# ATTiny85_Programmer_Arduino_Shield.net
KiCad netlist of a schematic drawn in EAGLE
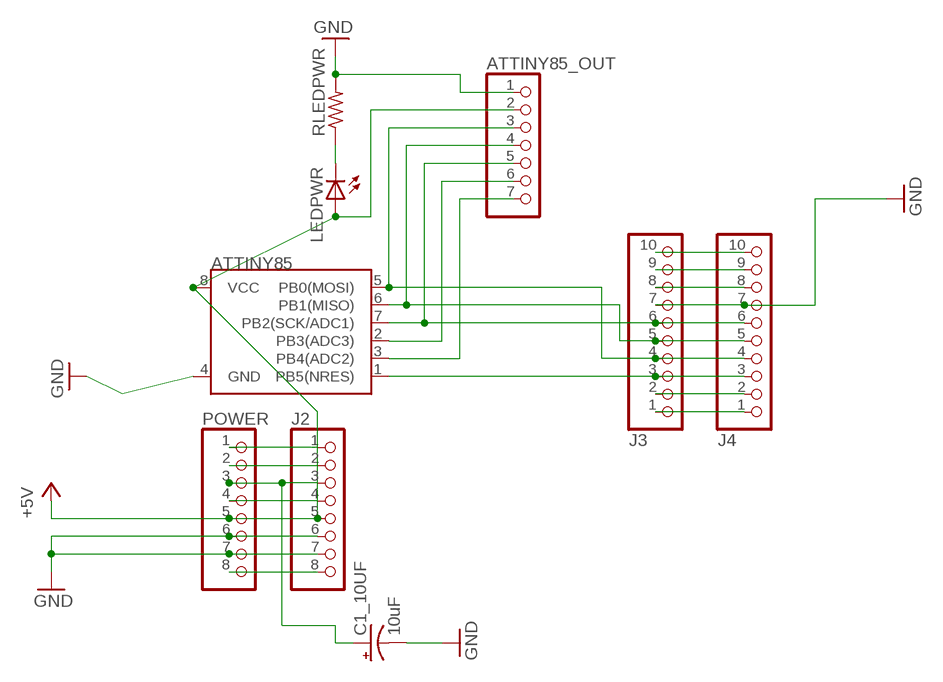
[diagram p0: schematic, sheet 1]

(export (version "E")
  (design (tool "Eeschema 10.0.6"))
  (components
    (comp (ref "ATTINY85")
      (value "TINY85-20-DIP")
      (footprint "eagle-import:DIP08")
      (libsource (lib "eagle-import") (part "ATTINY45TINY85-20-DIP"))
    )
    (comp (ref "ATTINY85_OUT")
      (value "PINHD-1X7")
      (footprint "eagle-import:1X07")
      (libsource (lib "eagle-import") (part "PINHD-1X7"))
    )
    (comp (ref "C1_10UF")
      (value "10uF")
      (footprint "eagle-import:EIA3216")
      (libsource (lib "eagle-import") (part "10UF-16V-10%(TANT)"))
    )
    (comp (ref "J2")
      (value "PINHD-1X8TH")
      (footprint "eagle-import:1X08-TH")
      (libsource (lib "eagle-import") (part "PINHD-1X8TH"))
    )
    (comp (ref "J3")
      (value "PINHD-1X10TH")
      (footprint "eagle-import:1X10-TH")
      (libsource (lib "eagle-import") (part "PINHD-1X10TH"))
    )
    (comp (ref "J4")
      (value "PINHD-1X10TH")
      (footprint "eagle-import:1X10-TH")
      (libsource (lib "eagle-import") (part "PINHD-1X10TH"))
    )
    (comp (ref "LEDPWR")
      (value "LEDCHIPLED_0805")
      (footprint "eagle-import:CHIPLED_0805")
      (libsource (lib "eagle-import") (part "LEDCHIPLED_0805"))
    )
    (comp (ref "POWER")
      (value "PINHD-1X8TH")
      (footprint "eagle-import:1X08-TH")
      (libsource (lib "eagle-import") (part "PINHD-1X8TH"))
    )
    (comp (ref "RLEDPWR")
      (value "R-US_R0805")
      (footprint "eagle-import:R0805")
      (libsource (lib "eagle-import") (part "R-US_R0805"))
    )
  )
  (nets
    (net (code "1") (name "+5V") (class "Default")
      (node (ref "ATTINY85") (pin "8") (pinfunction "VCC_8") (pintype "bidirectional"))
      (node (ref "ATTINY85_OUT") (pin "2") (pinfunction "2_2") (pintype "passive"))
      (node (ref "J2") (pin "5") (pinfunction "5_5") (pintype "passive"))
      (node (ref "LEDPWR") (pin "A") (pinfunction "A_A") (pintype "passive"))
      (node (ref "POWER") (pin "5") (pinfunction "5_5") (pintype "passive"))
    )
    (net (code "2") (name "GND") (class "Default")
      (node (ref "ATTINY85") (pin "4") (pinfunction "GND_4") (pintype "bidirectional"))
      (node (ref "ATTINY85_OUT") (pin "1") (pinfunction "1_1") (pintype "passive"))
      (node (ref "C1_10UF") (pin "C") (pinfunction "-_C") (pintype "passive"))
      (node (ref "J2") (pin "7") (pinfunction "7_7") (pintype "passive"))
      (node (ref "J3") (pin "7") (pinfunction "7_7") (pintype "passive"))
      (node (ref "J4") (pin "7") (pinfunction "7_7") (pintype "passive"))
      (node (ref "POWER") (pin "7") (pinfunction "7_7") (pintype "passive"))
      (node (ref "RLEDPWR") (pin "2") (pinfunction "2_2") (pintype "passive"))
    )
    (net (code "3") (name "Net-(ATTINY85-PB0(MOSI))") (class "Default")
      (node (ref "ATTINY85") (pin "5") (pinfunction "PB0(MOSI)_5") (pintype "bidirectional"))
      (node (ref "ATTINY85_OUT") (pin "3") (pinfunction "3_3") (pintype "passive"))
      (node (ref "J3") (pin "4") (pinfunction "4_4") (pintype "passive"))
      (node (ref "J4") (pin "4") (pinfunction "4_4") (pintype "passive"))
    )
    (net (code "4") (name "Net-(ATTINY85-PB1(MISO))") (class "Default")
      (node (ref "ATTINY85") (pin "6") (pinfunction "PB1(MISO)_6") (pintype "bidirectional"))
      (node (ref "ATTINY85_OUT") (pin "4") (pinfunction "4_4") (pintype "passive"))
      (node (ref "J3") (pin "5") (pinfunction "5_5") (pintype "passive"))
      (node (ref "J4") (pin "5") (pinfunction "5_5") (pintype "passive"))
    )
    (net (code "5") (name "Net-(ATTINY85-PB2(SCK{slash}ADC1))") (class "Default")
      (node (ref "ATTINY85") (pin "7") (pinfunction "PB2(SCK/ADC1)_7") (pintype "bidirectional"))
      (node (ref "ATTINY85_OUT") (pin "5") (pinfunction "5_5") (pintype "passive"))
      (node (ref "J3") (pin "6") (pinfunction "6_6") (pintype "passive"))
      (node (ref "J4") (pin "6") (pinfunction "6_6") (pintype "passive"))
    )
    (net (code "6") (name "Net-(ATTINY85-PB3(ADC3))") (class "Default")
      (node (ref "ATTINY85") (pin "2") (pinfunction "PB3(ADC3)_2") (pintype "bidirectional"))
      (node (ref "ATTINY85_OUT") (pin "6") (pinfunction "6_6") (pintype "passive"))
    )
    (net (code "7") (name "Net-(ATTINY85-PB4(ADC2))") (class "Default")
      (node (ref "ATTINY85") (pin "3") (pinfunction "PB4(ADC2)_3") (pintype "bidirectional"))
      (node (ref "ATTINY85_OUT") (pin "7") (pinfunction "7_7") (pintype "passive"))
    )
    (net (code "8") (name "Net-(ATTINY85-PB5(NRES))") (class "Default")
      (node (ref "ATTINY85") (pin "1") (pinfunction "PB5(NRES)_1") (pintype "bidirectional"))
      (node (ref "J3") (pin "3") (pinfunction "3_3") (pintype "passive"))
      (node (ref "J4") (pin "3") (pinfunction "3_3") (pintype "passive"))
    )
    (net (code "9") (name "Net-(C1_10UF-+)") (class "Default")
      (node (ref "C1_10UF") (pin "A") (pinfunction "+_A") (pintype "passive"))
      (node (ref "J2") (pin "3") (pinfunction "3_3") (pintype "passive"))
      (node (ref "POWER") (pin "3") (pinfunction "3_3") (pintype "passive"))
    )
    (net (code "10") (name "Net-(J2-Pad1)") (class "Default")
      (node (ref "J2") (pin "1") (pinfunction "1_1") (pintype "passive"))
      (node (ref "POWER") (pin "1") (pinfunction "1_1") (pintype "passive"))
    )
    (net (code "11") (name "Net-(J2-Pad2)") (class "Default")
      (node (ref "J2") (pin "2") (pinfunction "2_2") (pintype "passive"))
      (node (ref "POWER") (pin "2") (pinfunction "2_2") (pintype "passive"))
    )
    (net (code "12") (name "Net-(J2-Pad4)") (class "Default")
      (node (ref "J2") (pin "4") (pinfunction "4_4") (pintype "passive"))
      (node (ref "POWER") (pin "4") (pinfunction "4_4") (pintype "passive"))
    )
    (net (code "13") (name "Net-(J2-Pad6)") (class "Default")
      (node (ref "J2") (pin "6") (pinfunction "6_6") (pintype "passive"))
      (node (ref "POWER") (pin "6") (pinfunction "6_6") (pintype "passive"))
    )
    (net (code "14") (name "Net-(J2-Pad8)") (class "Default")
      (node (ref "J2") (pin "8") (pinfunction "8_8") (pintype "passive"))
      (node (ref "POWER") (pin "8") (pinfunction "8_8") (pintype "passive"))
    )
    (net (code "15") (name "Net-(J3-Pad1)") (class "Default")
      (node (ref "J3") (pin "1") (pinfunction "1_1") (pintype "passive"))
      (node (ref "J4") (pin "1") (pinfunction "1_1") (pintype "passive"))
    )
    (net (code "16") (name "Net-(J3-Pad2)") (class "Default")
      (node (ref "J3") (pin "2") (pinfunction "2_2") (pintype "passive"))
      (node (ref "J4") (pin "2") (pinfunction "2_2") (pintype "passive"))
    )
    (net (code "17") (name "Net-(J3-Pad8)") (class "Default")
      (node (ref "J3") (pin "8") (pinfunction "8_8") (pintype "passive"))
      (node (ref "J4") (pin "8") (pinfunction "8_8") (pintype "passive"))
    )
    (net (code "18") (name "Net-(J3-Pad9)") (class "Default")
      (node (ref "J3") (pin "9") (pinfunction "9_9") (pintype "passive"))
      (node (ref "J4") (pin "9") (pinfunction "9_9") (pintype "passive"))
    )
    (net (code "19") (name "Net-(J3-Pad10)") (class "Default")
      (node (ref "J3") (pin "10") (pinfunction "10_10") (pintype "passive"))
      (node (ref "J4") (pin "10") (pinfunction "10_10") (pintype "passive"))
    )
    (net (code "20") (name "Net-(LEDPWR-PadC)") (class "Default")
      (node (ref "LEDPWR") (pin "C") (pinfunction "C_C") (pintype "passive"))
      (node (ref "RLEDPWR") (pin "1") (pinfunction "1_1") (pintype "passive"))
    )
  )
)
